# MoteinoPi.net
KiCad netlist of a schematic drawn in EAGLE
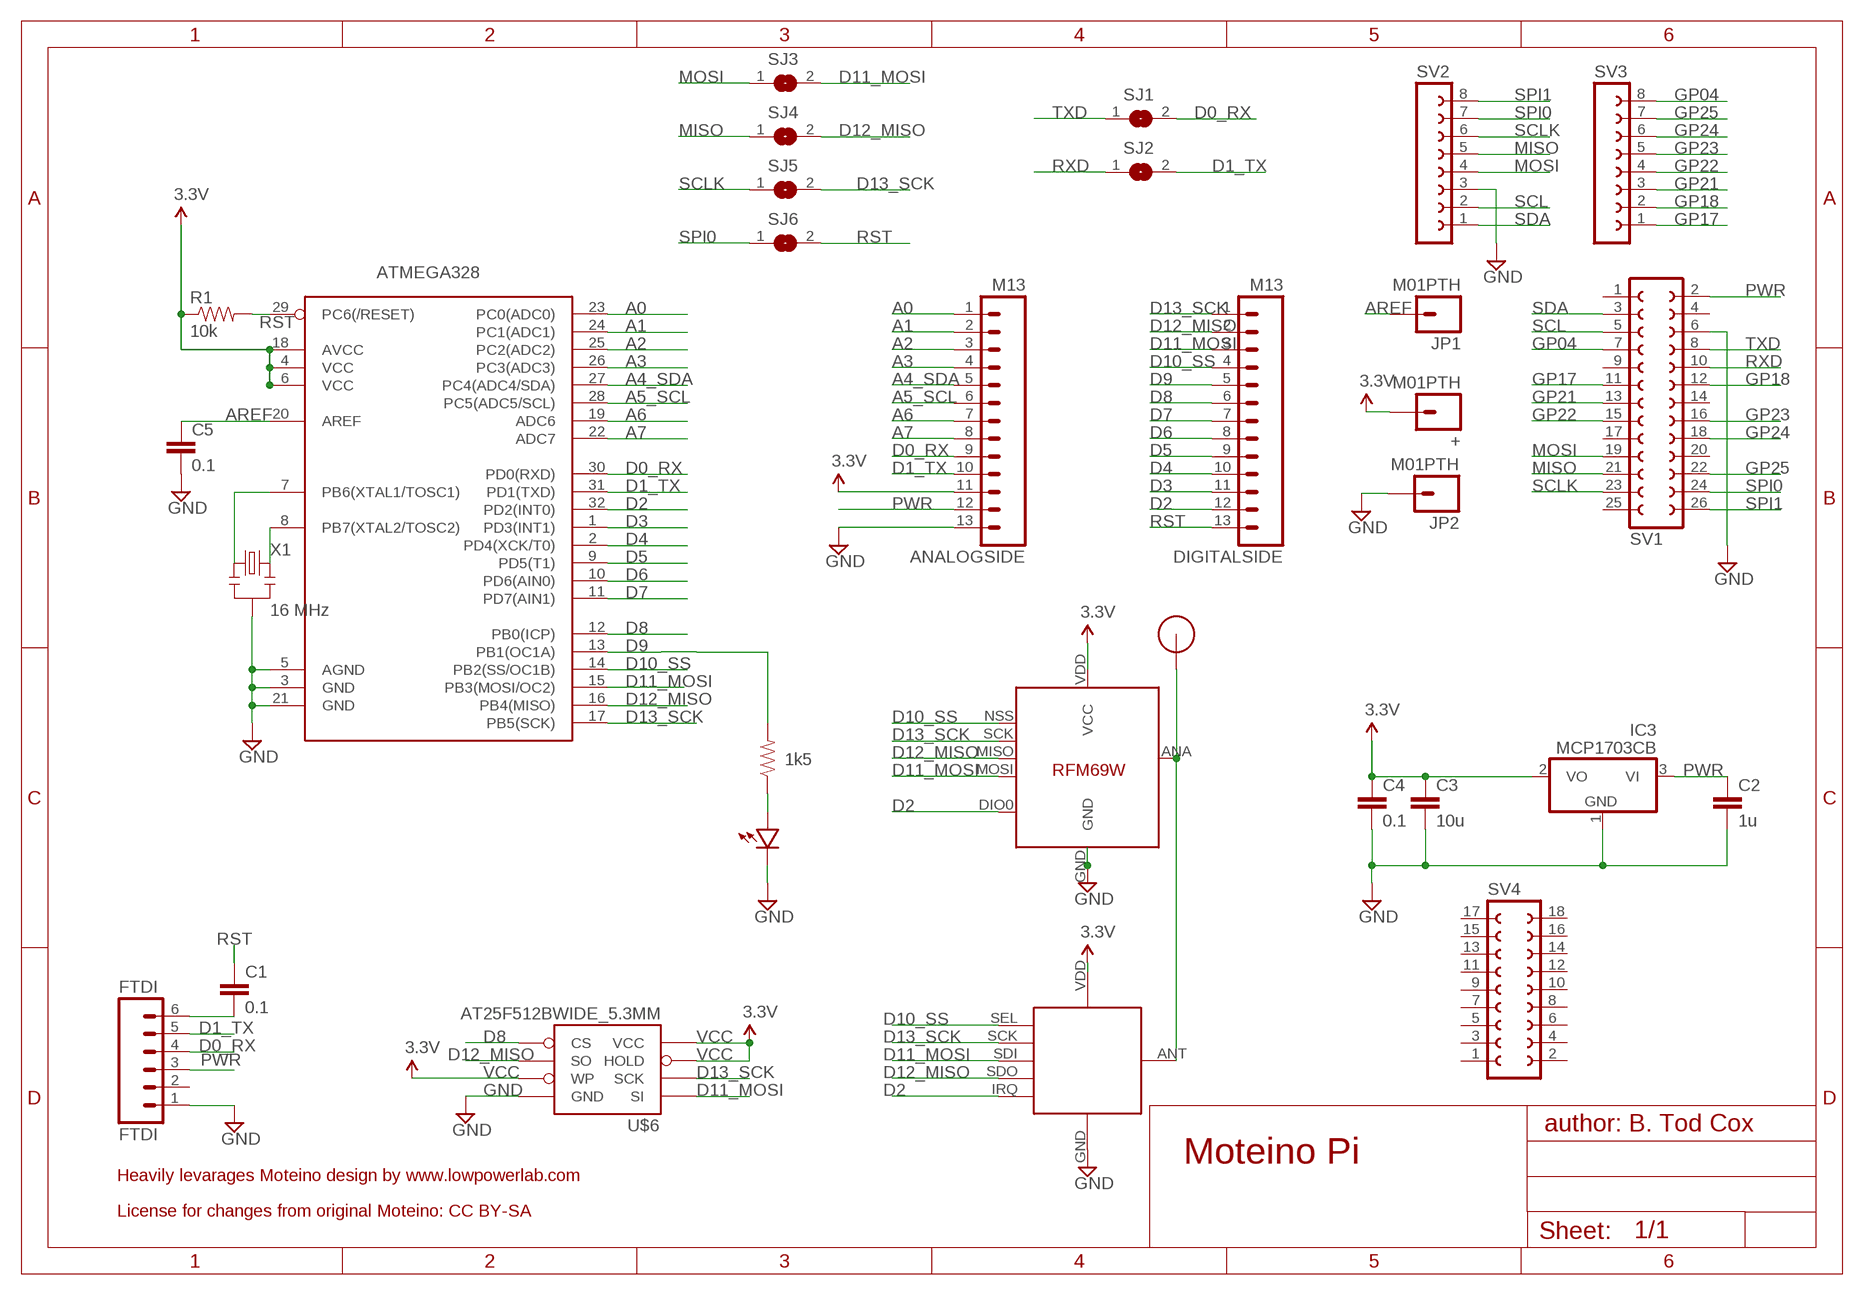
[diagram p0: schematic, sheet 1]

(export (version "E")
  (design (tool "Eeschema 10.0.6"))
  (components
    (comp (ref "+")
      (value "M01PTH")
      (footprint "eagle-import:1X01")
      (libsource (lib "eagle-import") (part "M01PTH"))
    )
    (comp (ref "ANALOGSIDE")
      (value "M13")
      (footprint "eagle-import:1X13")
      (libsource (lib "eagle-import") (part "M13"))
    )
    (comp (ref "ATMEGA328")
      (value "ATMega-328")
      (footprint "eagle-import:TQFP32-08")
      (libsource (lib "eagle-import") (part "ATMEGA168/328TQFP32"))
    )
    (comp (ref "C1")
      (value "0.1")
      (footprint "eagle-import:0603-CAP")
      (libsource (lib "eagle-import") (part "CAP0603-CAP"))
    )
    (comp (ref "C2")
      (value "1u")
      (footprint "eagle-import:0603-CAP")
      (libsource (lib "eagle-import") (part "CAP0603-CAP"))
    )
    (comp (ref "C3")
      (value "10u")
      (footprint "eagle-import:0805-CAP")
      (libsource (lib "eagle-import") (part "CAP0805-CAP"))
    )
    (comp (ref "C4")
      (value "0.1")
      (footprint "eagle-import:0603-CAP")
      (libsource (lib "eagle-import") (part "CAP0603-CAP"))
    )
    (comp (ref "C5")
      (value "0.1")
      (footprint "eagle-import:0603-CAP")
      (libsource (lib "eagle-import") (part "CAP0603-CAP"))
    )
    (comp (ref "DIGITALSIDE")
      (value "M13")
      (footprint "eagle-import:1X13")
      (libsource (lib "eagle-import") (part "M13"))
    )
    (comp (ref "FTDI")
      (value "FTDI")
      (footprint "eagle-import:1X06")
      (libsource (lib "eagle-import") (part "M06SIP"))
    )
    (comp (ref "IC3")
      (value "MCP1703CB")
      (footprint "eagle-import:SOT23")
      (libsource (lib "eagle-import") (part "MCP1703CB"))
    )
    (comp (ref "JP1")
      (value "M01PTH")
      (footprint "eagle-import:1X01")
      (libsource (lib "eagle-import") (part "M01PTH"))
    )
    (comp (ref "JP2")
      (value "M01PTH")
      (footprint "eagle-import:1X01")
      (libsource (lib "eagle-import") (part "M01PTH"))
    )
    (comp (ref "R1")
      (value "10k")
      (footprint "eagle-import:0603-RES")
      (libsource (lib "eagle-import") (part "RESISTOR0603-RES"))
    )
    (comp (ref "R2")
      (value "1k5")
      (footprint "eagle-import:0603-RES")
      (libsource (lib "eagle-import") (part "RESISTOR0603-RES"))
    )
    (comp (ref "RFM12B")
      (value "RFM12B_MINPADS")
      (footprint "eagle-import:RFM12B-MINPADS")
      (libsource (lib "eagle-import") (part "RFM12B_MINPADS"))
    )
    (comp (ref "SJ1") (value "SJ") (footprint "eagle-import:SJ") (libsource (lib "eagle-import") (part "SJ")))
    (comp (ref "SJ2") (value "SJ") (footprint "eagle-import:SJ") (libsource (lib "eagle-import") (part "SJ")))
    (comp (ref "SJ3") (value "SJ") (footprint "eagle-import:SJ") (libsource (lib "eagle-import") (part "SJ")))
    (comp (ref "SJ4") (value "SJ") (footprint "eagle-import:SJ") (libsource (lib "eagle-import") (part "SJ")))
    (comp (ref "SJ5") (value "SJ") (footprint "eagle-import:SJ") (libsource (lib "eagle-import") (part "SJ")))
    (comp (ref "SJ6") (value "SJ") (footprint "eagle-import:SJ") (libsource (lib "eagle-import") (part "SJ")))
    (comp (ref "SV1")
      (value "FE13-2")
      (footprint "eagle-import:FE13-2")
      (libsource (lib "eagle-import") (part "FE13-2"))
    )
    (comp (ref "SV2")
      (value "FE08-1")
      (footprint "eagle-import:FE08")
      (libsource (lib "eagle-import") (part "FE08-1"))
    )
    (comp (ref "SV3")
      (value "FE08-1")
      (footprint "eagle-import:FE08")
      (libsource (lib "eagle-import") (part "FE08-1"))
    )
    (comp (ref "SV4")
      (value "FE09-2")
      (footprint "eagle-import:FE09-2")
      (libsource (lib "eagle-import") (part "FE09-2"))
    )
    (comp (ref "U$1")
      (value "RFM12B_ANTENNA")
      (footprint "eagle-import:RFM12B-ANTENNA")
      (libsource (lib "eagle-import") (part "RFM12B_ANTENNA"))
    )
    (comp (ref "U$2")
      (value "LED0603")
      (footprint "eagle-import:0603-LED")
      (libsource (lib "eagle-import") (part "LED0603"))
    )
    (comp (ref "U$5")
      (value "RFM69")
      (footprint "eagle-import:RFM69W-MINPADS")
      (libsource (lib "eagle-import") (part "RFM69"))
    )
    (comp (ref "U$6")
      (value "AT25F512BWIDE_5.3MM")
      (footprint "eagle-import:SO08WIDE")
      (libsource (lib "eagle-import") (part "AT25F512BWIDE_5.3MM"))
    )
    (comp (ref "X1")
      (value "16 MHz")
      (footprint "eagle-import:RESONATOR-SMD")
      (libsource (lib "eagle-import") (part "RESONATORSMD"))
    )
  )
  (nets
    (net (code "1") (name "/A0") (class "Default")
      (node (ref "ANALOGSIDE") (pin "1") (pinfunction "1_1") (pintype "passive"))
      (node (ref "ATMEGA328") (pin "23") (pinfunction "PC0(ADC0)_23") (pintype "bidirectional"))
    )
    (net (code "2") (name "/A1") (class "Default")
      (node (ref "ANALOGSIDE") (pin "2") (pinfunction "2_2") (pintype "passive"))
      (node (ref "ATMEGA328") (pin "24") (pinfunction "PC1(ADC1)_24") (pintype "bidirectional"))
    )
    (net (code "3") (name "/A2") (class "Default")
      (node (ref "ANALOGSIDE") (pin "3") (pinfunction "3_3") (pintype "passive"))
      (node (ref "ATMEGA328") (pin "25") (pinfunction "PC2(ADC2)_25") (pintype "bidirectional"))
    )
    (net (code "4") (name "/A3") (class "Default")
      (node (ref "ANALOGSIDE") (pin "4") (pinfunction "4_4") (pintype "passive"))
      (node (ref "ATMEGA328") (pin "26") (pinfunction "PC3(ADC3)_26") (pintype "bidirectional"))
    )
    (net (code "5") (name "/A4_SDA") (class "Default")
      (node (ref "ANALOGSIDE") (pin "5") (pinfunction "5_5") (pintype "passive"))
      (node (ref "ATMEGA328") (pin "27") (pinfunction "PC4(ADC4/SDA)_27") (pintype "bidirectional"))
    )
    (net (code "6") (name "/A5_SCL") (class "Default")
      (node (ref "ANALOGSIDE") (pin "6") (pinfunction "6_6") (pintype "passive"))
      (node (ref "ATMEGA328") (pin "28") (pinfunction "PC5(ADC5/SCL)_28") (pintype "bidirectional"))
    )
    (net (code "7") (name "/A6") (class "Default")
      (node (ref "ANALOGSIDE") (pin "7") (pinfunction "7_7") (pintype "passive"))
      (node (ref "ATMEGA328") (pin "19") (pinfunction "ADC6_19") (pintype "bidirectional"))
    )
    (net (code "8") (name "/A7") (class "Default")
      (node (ref "ANALOGSIDE") (pin "8") (pinfunction "8_8") (pintype "passive"))
      (node (ref "ATMEGA328") (pin "22") (pinfunction "ADC7_22") (pintype "bidirectional"))
    )
    (net (code "9") (name "/AREF") (class "Default")
      (node (ref "ATMEGA328") (pin "20") (pinfunction "AREF_20") (pintype "bidirectional"))
      (node (ref "C5") (pin "1") (pinfunction "1_1") (pintype "passive"))
      (node (ref "JP1") (pin "1") (pinfunction "1_1") (pintype "passive"))
    )
    (net (code "10") (name "/D0_RX") (class "Default")
      (node (ref "ANALOGSIDE") (pin "9") (pinfunction "9_9") (pintype "passive"))
      (node (ref "ATMEGA328") (pin "30") (pinfunction "PD0(RXD)_30") (pintype "bidirectional"))
      (node (ref "FTDI") (pin "4") (pinfunction "4_4") (pintype "passive"))
      (node (ref "SJ1") (pin "2") (pinfunction "2_2") (pintype "passive"))
    )
    (net (code "11") (name "/D1_TX") (class "Default")
      (node (ref "ANALOGSIDE") (pin "10") (pinfunction "10_10") (pintype "passive"))
      (node (ref "ATMEGA328") (pin "31") (pinfunction "PD1(TXD)_31") (pintype "bidirectional"))
      (node (ref "FTDI") (pin "5") (pinfunction "5_5") (pintype "passive"))
      (node (ref "SJ2") (pin "2") (pinfunction "2_2") (pintype "passive"))
    )
    (net (code "12") (name "/D2") (class "Default")
      (node (ref "ATMEGA328") (pin "32") (pinfunction "PD2(INT0)_32") (pintype "bidirectional"))
      (node (ref "DIGITALSIDE") (pin "12") (pinfunction "12_12") (pintype "passive"))
      (node (ref "RFM12B") (pin "IRQ") (pinfunction "IRQ_IRQ") (pintype "bidirectional"))
      (node (ref "U$5") (pin "DIO0") (pinfunction "DIO0_DIO0") (pintype "open_collector"))
    )
    (net (code "13") (name "/D3") (class "Default")
      (node (ref "ATMEGA328") (pin "1") (pinfunction "PD3(INT1)_1") (pintype "bidirectional"))
      (node (ref "DIGITALSIDE") (pin "11") (pinfunction "11_11") (pintype "passive"))
    )
    (net (code "14") (name "/D4") (class "Default")
      (node (ref "ATMEGA328") (pin "2") (pinfunction "PD4(XCK/T0)_2") (pintype "bidirectional"))
      (node (ref "DIGITALSIDE") (pin "10") (pinfunction "10_10") (pintype "passive"))
    )
    (net (code "15") (name "/D5") (class "Default")
      (node (ref "ATMEGA328") (pin "9") (pinfunction "PD5(T1)_9") (pintype "bidirectional"))
      (node (ref "DIGITALSIDE") (pin "9") (pinfunction "9_9") (pintype "passive"))
    )
    (net (code "16") (name "/D6") (class "Default")
      (node (ref "ATMEGA328") (pin "10") (pinfunction "PD6(AIN0)_10") (pintype "bidirectional"))
      (node (ref "DIGITALSIDE") (pin "8") (pinfunction "8_8") (pintype "passive"))
    )
    (net (code "17") (name "/D7") (class "Default")
      (node (ref "ATMEGA328") (pin "11") (pinfunction "PD7(AIN1)_11") (pintype "bidirectional"))
      (node (ref "DIGITALSIDE") (pin "7") (pinfunction "7_7") (pintype "passive"))
    )
    (net (code "18") (name "/D8") (class "Default")
      (node (ref "ATMEGA328") (pin "12") (pinfunction "PB0(ICP)_12") (pintype "bidirectional"))
      (node (ref "DIGITALSIDE") (pin "6") (pinfunction "6_6") (pintype "passive"))
      (node (ref "U$6") (pin "1") (pinfunction "CS_1") (pintype "bidirectional"))
    )
    (net (code "19") (name "/D9") (class "Default")
      (node (ref "ATMEGA328") (pin "13") (pinfunction "PB1(OC1A)_13") (pintype "bidirectional"))
      (node (ref "DIGITALSIDE") (pin "5") (pinfunction "5_5") (pintype "passive"))
      (node (ref "R2") (pin "2") (pinfunction "2_2") (pintype "passive"))
    )
    (net (code "20") (name "/D10_SS") (class "Default")
      (node (ref "ATMEGA328") (pin "14") (pinfunction "PB2(SS/OC1B)_14") (pintype "bidirectional"))
      (node (ref "DIGITALSIDE") (pin "4") (pinfunction "4_4") (pintype "passive"))
      (node (ref "RFM12B") (pin "SEL") (pinfunction "SEL_SEL") (pintype "bidirectional"))
      (node (ref "U$5") (pin "NSS") (pinfunction "SEL_NSS") (pintype "input"))
    )
    (net (code "21") (name "/D11_MOSI") (class "Default")
      (node (ref "ATMEGA328") (pin "15") (pinfunction "PB3(MOSI/OC2)_15") (pintype "bidirectional"))
      (node (ref "DIGITALSIDE") (pin "3") (pinfunction "3_3") (pintype "passive"))
      (node (ref "RFM12B") (pin "SDI") (pinfunction "SDI/MOSI_SDI") (pintype "bidirectional"))
      (node (ref "SJ3") (pin "2") (pinfunction "2_2") (pintype "passive"))
      (node (ref "U$5") (pin "MOSI") (pinfunction "MOSI_MOSI") (pintype "output"))
      (node (ref "U$6") (pin "5") (pinfunction "SI_5") (pintype "bidirectional"))
    )
    (net (code "22") (name "/D12_MISO") (class "Default")
      (node (ref "ATMEGA328") (pin "16") (pinfunction "PB4(MISO)_16") (pintype "bidirectional"))
      (node (ref "DIGITALSIDE") (pin "2") (pinfunction "2_2") (pintype "passive"))
      (node (ref "RFM12B") (pin "SDO") (pinfunction "SDO/MISO_SDO") (pintype "bidirectional"))
      (node (ref "SJ4") (pin "2") (pinfunction "2_2") (pintype "passive"))
      (node (ref "U$5") (pin "MISO") (pinfunction "MISO_MISO") (pintype "input"))
      (node (ref "U$6") (pin "2") (pinfunction "SO_2") (pintype "bidirectional"))
    )
    (net (code "23") (name "/D13_SCK") (class "Default")
      (node (ref "ATMEGA328") (pin "17") (pinfunction "PB5(SCK)_17") (pintype "bidirectional"))
      (node (ref "DIGITALSIDE") (pin "1") (pinfunction "1_1") (pintype "passive"))
      (node (ref "RFM12B") (pin "SCK") (pinfunction "SCK_SCK") (pintype "bidirectional"))
      (node (ref "SJ5") (pin "2") (pinfunction "2_2") (pintype "passive"))
      (node (ref "U$5") (pin "SCK") (pinfunction "SCK_SCK") (pintype "input"))
      (node (ref "U$6") (pin "6") (pinfunction "SCK_6") (pintype "bidirectional"))
    )
    (net (code "24") (name "/GP04") (class "Default")
      (node (ref "SV1") (pin "7") (pinfunction "7_7") (pintype "passive"))
      (node (ref "SV3") (pin "8") (pinfunction "8_8") (pintype "passive"))
    )
    (net (code "25") (name "/GP17") (class "Default")
      (node (ref "SV1") (pin "11") (pinfunction "11_11") (pintype "passive"))
      (node (ref "SV3") (pin "1") (pinfunction "1_1") (pintype "passive"))
    )
    (net (code "26") (name "/GP18") (class "Default")
      (node (ref "SV1") (pin "12") (pinfunction "12_12") (pintype "passive"))
      (node (ref "SV3") (pin "2") (pinfunction "2_2") (pintype "passive"))
    )
    (net (code "27") (name "/GP21") (class "Default")
      (node (ref "SV1") (pin "13") (pinfunction "13_13") (pintype "passive"))
      (node (ref "SV3") (pin "3") (pinfunction "3_3") (pintype "passive"))
    )
    (net (code "28") (name "/GP22") (class "Default")
      (node (ref "SV1") (pin "15") (pinfunction "15_15") (pintype "passive"))
      (node (ref "SV3") (pin "4") (pinfunction "4_4") (pintype "passive"))
    )
    (net (code "29") (name "/GP23") (class "Default")
      (node (ref "SV1") (pin "16") (pinfunction "16_16") (pintype "passive"))
      (node (ref "SV3") (pin "5") (pinfunction "5_5") (pintype "passive"))
    )
    (net (code "30") (name "/GP24") (class "Default")
      (node (ref "SV1") (pin "18") (pinfunction "18_18") (pintype "passive"))
      (node (ref "SV3") (pin "6") (pinfunction "6_6") (pintype "passive"))
    )
    (net (code "31") (name "/GP25") (class "Default")
      (node (ref "SV1") (pin "22") (pinfunction "22_22") (pintype "passive"))
      (node (ref "SV3") (pin "7") (pinfunction "7_7") (pintype "passive"))
    )
    (net (code "32") (name "/MISO") (class "Default")
      (node (ref "SJ4") (pin "1") (pinfunction "1_1") (pintype "passive"))
      (node (ref "SV1") (pin "21") (pinfunction "21_21") (pintype "passive"))
      (node (ref "SV2") (pin "5") (pinfunction "5_5") (pintype "passive"))
    )
    (net (code "33") (name "/MOSI") (class "Default")
      (node (ref "SJ3") (pin "1") (pinfunction "1_1") (pintype "passive"))
      (node (ref "SV1") (pin "19") (pinfunction "19_19") (pintype "passive"))
      (node (ref "SV2") (pin "4") (pinfunction "4_4") (pintype "passive"))
    )
    (net (code "34") (name "/PWR") (class "Default")
      (node (ref "ANALOGSIDE") (pin "12") (pinfunction "12_12") (pintype "passive"))
      (node (ref "C2") (pin "1") (pinfunction "1_1") (pintype "passive"))
      (node (ref "FTDI") (pin "3") (pinfunction "3_3") (pintype "passive"))
      (node (ref "IC3") (pin "3") (pinfunction "VI_3") (pintype "input"))
      (node (ref "SV1") (pin "2") (pinfunction "2_2") (pintype "passive"))
    )
    (net (code "35") (name "/RST") (class "Default")
      (node (ref "ATMEGA328") (pin "29") (pinfunction "PC6(/RESET)_29") (pintype "bidirectional"))
      (node (ref "C1") (pin "1") (pinfunction "1_1") (pintype "passive"))
      (node (ref "DIGITALSIDE") (pin "13") (pinfunction "13_13") (pintype "passive"))
      (node (ref "R1") (pin "2") (pinfunction "2_2") (pintype "passive"))
      (node (ref "SJ6") (pin "2") (pinfunction "2_2") (pintype "passive"))
    )
    (net (code "36") (name "/RXD") (class "Default")
      (node (ref "SJ2") (pin "1") (pinfunction "1_1") (pintype "passive"))
      (node (ref "SV1") (pin "10") (pinfunction "10_10") (pintype "passive"))
    )
    (net (code "37") (name "/SCL") (class "Default")
      (node (ref "SV1") (pin "5") (pinfunction "5_5") (pintype "passive"))
      (node (ref "SV2") (pin "2") (pinfunction "2_2") (pintype "passive"))
    )
    (net (code "38") (name "/SCLK") (class "Default")
      (node (ref "SJ5") (pin "1") (pinfunction "1_1") (pintype "passive"))
      (node (ref "SV1") (pin "23") (pinfunction "23_23") (pintype "passive"))
      (node (ref "SV2") (pin "6") (pinfunction "6_6") (pintype "passive"))
    )
    (net (code "39") (name "/SDA") (class "Default")
      (node (ref "SV1") (pin "3") (pinfunction "3_3") (pintype "passive"))
      (node (ref "SV2") (pin "1") (pinfunction "1_1") (pintype "passive"))
    )
    (net (code "40") (name "/SPI0") (class "Default")
      (node (ref "SJ6") (pin "1") (pinfunction "1_1") (pintype "passive"))
      (node (ref "SV1") (pin "24") (pinfunction "24_24") (pintype "passive"))
      (node (ref "SV2") (pin "7") (pinfunction "7_7") (pintype "passive"))
    )
    (net (code "41") (name "/SPI1") (class "Default")
      (node (ref "SV1") (pin "26") (pinfunction "26_26") (pintype "passive"))
      (node (ref "SV2") (pin "8") (pinfunction "8_8") (pintype "passive"))
    )
    (net (code "42") (name "/TXD") (class "Default")
      (node (ref "SJ1") (pin "1") (pinfunction "1_1") (pintype "passive"))
      (node (ref "SV1") (pin "8") (pinfunction "8_8") (pintype "passive"))
    )
    (net (code "43") (name "3.3V") (class "Default")
      (node (ref "+") (pin "1") (pinfunction "1_1") (pintype "passive"))
      (node (ref "ANALOGSIDE") (pin "11") (pinfunction "11_11") (pintype "passive"))
      (node (ref "ATMEGA328") (pin "18") (pinfunction "AVCC_18") (pintype "bidirectional"))
      (node (ref "ATMEGA328") (pin "4") (pinfunction "VCC_4") (pintype "bidirectional"))
      (node (ref "ATMEGA328") (pin "6") (pinfunction "VCC_6") (pintype "bidirectional"))
      (node (ref "C3") (pin "1") (pinfunction "1_1") (pintype "passive"))
      (node (ref "C4") (pin "1") (pinfunction "1_1") (pintype "passive"))
      (node (ref "IC3") (pin "2") (pinfunction "VO_2") (pintype "passive"))
      (node (ref "R1") (pin "1") (pinfunction "1_1") (pintype "passive"))
      (node (ref "RFM12B") (pin "VDD") (pinfunction "VDD_VDD") (pintype "bidirectional"))
      (node (ref "U$5") (pin "VDD") (pinfunction "VCC_VDD") (pintype "power_in"))
      (node (ref "U$6") (pin "3") (pinfunction "WP_3") (pintype "bidirectional"))
      (node (ref "U$6") (pin "7") (pinfunction "HOLD_7") (pintype "bidirectional"))
      (node (ref "U$6") (pin "8") (pinfunction "VCC_8") (pintype "bidirectional"))
    )
    (net (code "44") (name "GND") (class "Default")
      (node (ref "ANALOGSIDE") (pin "13") (pinfunction "13_13") (pintype "passive"))
      (node (ref "ATMEGA328") (pin "21") (pinfunction "GND_21") (pintype "bidirectional"))
      (node (ref "ATMEGA328") (pin "3") (pinfunction "GND_3") (pintype "bidirectional"))
      (node (ref "ATMEGA328") (pin "5") (pinfunction "AGND_5") (pintype "bidirectional"))
      (node (ref "C2") (pin "2") (pinfunction "2_2") (pintype "passive"))
      (node (ref "C3") (pin "2") (pinfunction "2_2") (pintype "passive"))
      (node (ref "C4") (pin "2") (pinfunction "2_2") (pintype "passive"))
      (node (ref "C5") (pin "2") (pinfunction "2_2") (pintype "passive"))
      (node (ref "FTDI") (pin "1") (pinfunction "1_1") (pintype "passive"))
      (node (ref "IC3") (pin "1") (pinfunction "GND_1") (pintype "passive"))
      (node (ref "JP2") (pin "1") (pinfunction "1_1") (pintype "passive"))
      (node (ref "RFM12B") (pin "GND") (pinfunction "GND_GND") (pintype "bidirectional"))
      (node (ref "SV1") (pin "6") (pinfunction "6_6") (pintype "passive"))
      (node (ref "SV2") (pin "3") (pinfunction "3_3") (pintype "passive"))
      (node (ref "U$2") (pin "MINUS") (pinfunction "MINUS_MINUS") (pintype "passive"))
      (node (ref "U$5") (pin "GND") (pinfunction "GND_GND") (pintype "power_in"))
      (node (ref "U$6") (pin "4") (pinfunction "GND_4") (pintype "bidirectional"))
      (node (ref "X1") (pin "2") (pinfunction "2_2") (pintype "passive"))
    )
    (net (code "45") (name "Net-(ATMEGA328-PB6(XTAL1{slash}TOSC1))") (class "Default")
      (node (ref "ATMEGA328") (pin "7") (pinfunction "PB6(XTAL1/TOSC1)_7") (pintype "bidirectional"))
      (node (ref "X1") (pin "1") (pinfunction "1_1") (pintype "passive"))
    )
    (net (code "46") (name "Net-(ATMEGA328-PB7(XTAL2{slash}TOSC2))") (class "Default")
      (node (ref "ATMEGA328") (pin "8") (pinfunction "PB7(XTAL2/TOSC2)_8") (pintype "bidirectional"))
      (node (ref "X1") (pin "3") (pinfunction "3_3") (pintype "passive"))
    )
    (net (code "47") (name "Net-(C1-Pad2)") (class "Default")
      (node (ref "C1") (pin "2") (pinfunction "2_2") (pintype "passive"))
      (node (ref "FTDI") (pin "6") (pinfunction "6_6") (pintype "passive"))
    )
    (net (code "48") (name "Net-(R2-Pad1)") (class "Default")
      (node (ref "R2") (pin "1") (pinfunction "1_1") (pintype "passive"))
      (node (ref "U$2") (pin "PLUS") (pinfunction "PLUS_PLUS") (pintype "passive"))
    )
    (net (code "49") (name "Net-(U$1-1)") (class "Default")
      (node (ref "RFM12B") (pin "ANT") (pinfunction "ANT_ANT") (pintype "bidirectional"))
      (node (ref "U$1") (pin "P$1") (pinfunction "1_P$1") (pintype "bidirectional"))
      (node (ref "U$5") (pin "ANA") (pinfunction "ANT_ANA") (pintype "passive"))
    )
    (net (code "50") (name "unconnected-(FTDI-Pad2)") (class "Default")
      (node (ref "FTDI") (pin "2") (pinfunction "2_2") (pintype "passive"))
    )
    (net (code "51") (name "unconnected-(SV1-Pad1)") (class "Default")
      (node (ref "SV1") (pin "1") (pinfunction "1_1") (pintype "passive"))
    )
    (net (code "52") (name "unconnected-(SV1-Pad4)") (class "Default")
      (node (ref "SV1") (pin "4") (pinfunction "4_4") (pintype "passive"))
    )
    (net (code "53") (name "unconnected-(SV1-Pad9)") (class "Default")
      (node (ref "SV1") (pin "9") (pinfunction "9_9") (pintype "passive"))
    )
    (net (code "54") (name "unconnected-(SV1-Pad14)") (class "Default")
      (node (ref "SV1") (pin "14") (pinfunction "14_14") (pintype "passive"))
    )
    (net (code "55") (name "unconnected-(SV1-Pad17)") (class "Default")
      (node (ref "SV1") (pin "17") (pinfunction "17_17") (pintype "passive"))
    )
    (net (code "56") (name "unconnected-(SV1-Pad20)") (class "Default")
      (node (ref "SV1") (pin "20") (pinfunction "20_20") (pintype "passive"))
    )
    (net (code "57") (name "unconnected-(SV1-Pad25)") (class "Default")
      (node (ref "SV1") (pin "25") (pinfunction "25_25") (pintype "passive"))
    )
    (net (code "58") (name "unconnected-(SV4-Pad1)") (class "Default")
      (node (ref "SV4") (pin "1") (pinfunction "1_1") (pintype "passive"))
    )
    (net (code "59") (name "unconnected-(SV4-Pad2)") (class "Default")
      (node (ref "SV4") (pin "2") (pinfunction "2_2") (pintype "passive"))
    )
    (net (code "60") (name "unconnected-(SV4-Pad3)") (class "Default")
      (node (ref "SV4") (pin "3") (pinfunction "3_3") (pintype "passive"))
    )
    (net (code "61") (name "unconnected-(SV4-Pad4)") (class "Default")
      (node (ref "SV4") (pin "4") (pinfunction "4_4") (pintype "passive"))
    )
    (net (code "62") (name "unconnected-(SV4-Pad5)") (class "Default")
      (node (ref "SV4") (pin "5") (pinfunction "5_5") (pintype "passive"))
    )
    (net (code "63") (name "unconnected-(SV4-Pad6)") (class "Default")
      (node (ref "SV4") (pin "6") (pinfunction "6_6") (pintype "passive"))
    )
    (net (code "64") (name "unconnected-(SV4-Pad7)") (class "Default")
      (node (ref "SV4") (pin "7") (pinfunction "7_7") (pintype "passive"))
    )
    (net (code "65") (name "unconnected-(SV4-Pad8)") (class "Default")
      (node (ref "SV4") (pin "8") (pinfunction "8_8") (pintype "passive"))
    )
    (net (code "66") (name "unconnected-(SV4-Pad9)") (class "Default")
      (node (ref "SV4") (pin "9") (pinfunction "9_9") (pintype "passive"))
    )
    (net (code "67") (name "unconnected-(SV4-Pad10)") (class "Default")
      (node (ref "SV4") (pin "10") (pinfunction "10_10") (pintype "passive"))
    )
    (net (code "68") (name "unconnected-(SV4-Pad11)") (class "Default")
      (node (ref "SV4") (pin "11") (pinfunction "11_11") (pintype "passive"))
    )
    (net (code "69") (name "unconnected-(SV4-Pad12)") (class "Default")
      (node (ref "SV4") (pin "12") (pinfunction "12_12") (pintype "passive"))
    )
    (net (code "70") (name "unconnected-(SV4-Pad13)") (class "Default")
      (node (ref "SV4") (pin "13") (pinfunction "13_13") (pintype "passive"))
    )
    (net (code "71") (name "unconnected-(SV4-Pad14)") (class "Default")
      (node (ref "SV4") (pin "14") (pinfunction "14_14") (pintype "passive"))
    )
    (net (code "72") (name "unconnected-(SV4-Pad15)") (class "Default")
      (node (ref "SV4") (pin "15") (pinfunction "15_15") (pintype "passive"))
    )
    (net (code "73") (name "unconnected-(SV4-Pad16)") (class "Default")
      (node (ref "SV4") (pin "16") (pinfunction "16_16") (pintype "passive"))
    )
    (net (code "74") (name "unconnected-(SV4-Pad17)") (class "Default")
      (node (ref "SV4") (pin "17") (pinfunction "17_17") (pintype "passive"))
    )
    (net (code "75") (name "unconnected-(SV4-Pad18)") (class "Default")
      (node (ref "SV4") (pin "18") (pinfunction "18_18") (pintype "passive"))
    )
  )
)
